# Power_Cerebro.net
KiCad netlist of a schematic drawn in Altium Designer
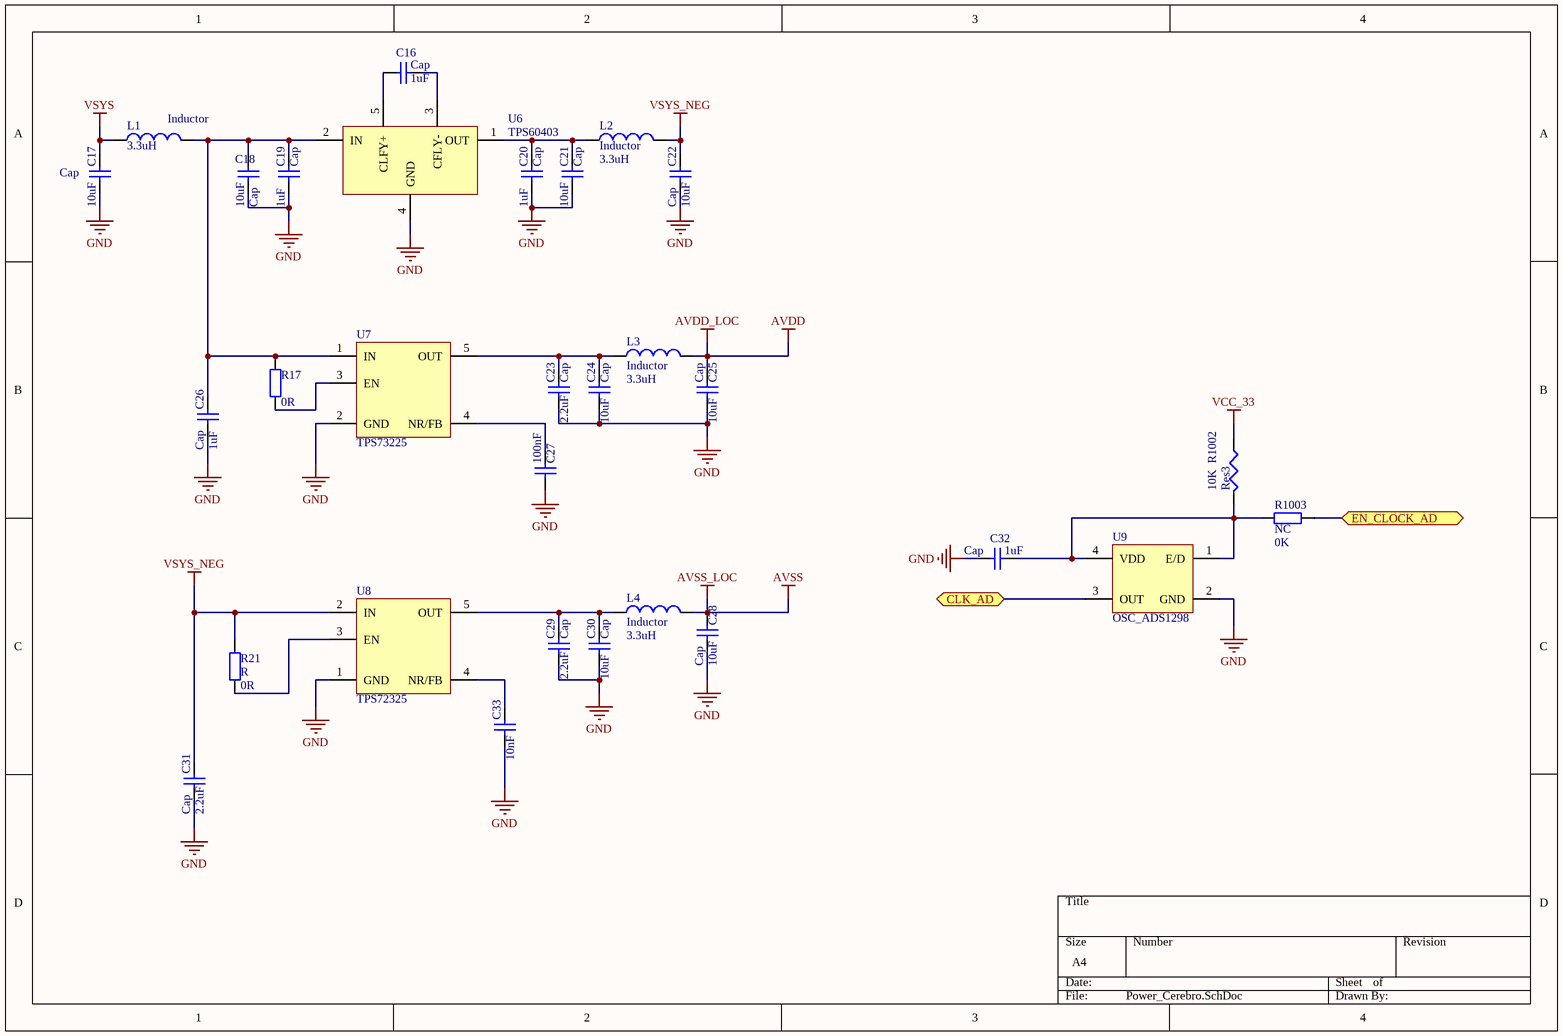
[diagram p0: Power_Cerebro.SchDoc]

(export (version "E")
  (design (tool "Eeschema 10.0.6"))
  (components
    (comp (ref "C16")
      (value "Cap")
      (footprint "cap_0402_R - modified")
      (description "Capacitor")
      (fields (field (name "ALTIUM_VALUE") "1uF") (field (name "PUBLISHER") "Altium Limited"))
      (libsource (lib "Miscellaneous Devices") (part "Cap"))
    )
    (comp (ref "C17")
      (value "Cap")
      (footprint "cap_0402_R - modified")
      (description "Capacitor")
      (fields (field (name "ALTIUM_VALUE") "10uF") (field (name "PUBLISHER") "Altium Limited"))
      (libsource (lib "Miscellaneous Devices") (part "Cap"))
    )
    (comp (ref "C18")
      (value "Cap")
      (footprint "cap_0402_R - modified")
      (description "Capacitor")
      (fields (field (name "ALTIUM_VALUE") "10uF") (field (name "PUBLISHER") "Altium Limited"))
      (libsource (lib "Miscellaneous Devices") (part "Cap"))
    )
    (comp (ref "C19")
      (value "Cap")
      (footprint "cap_0402_R - modified")
      (description "Capacitor")
      (fields (field (name "ALTIUM_VALUE") "1uF") (field (name "PUBLISHER") "Altium Limited"))
      (libsource (lib "Miscellaneous Devices") (part "Cap"))
    )
    (comp (ref "C20")
      (value "Cap")
      (footprint "cap_0402_R - modified")
      (description "Capacitor")
      (fields (field (name "ALTIUM_VALUE") "1uF") (field (name "PUBLISHER") "Altium Limited"))
      (libsource (lib "Miscellaneous Devices") (part "Cap"))
    )
    (comp (ref "C21")
      (value "Cap")
      (footprint "cap_0402_R - modified")
      (description "Capacitor")
      (fields (field (name "ALTIUM_VALUE") "10uF") (field (name "PUBLISHER") "Altium Limited"))
      (libsource (lib "Miscellaneous Devices") (part "Cap"))
    )
    (comp (ref "C22")
      (value "Cap")
      (footprint "cap_0402_R - modified")
      (description "Capacitor")
      (fields (field (name "ALTIUM_VALUE") "10uF") (field (name "PUBLISHER") "Altium Limited"))
      (libsource (lib "Miscellaneous Devices") (part "Cap"))
    )
    (comp (ref "C23")
      (value "Cap")
      (footprint "cap_0402_R - modified")
      (description "Capacitor")
      (fields (field (name "ALTIUM_VALUE") "2.2uF") (field (name "PUBLISHER") "Altium Limited"))
      (libsource (lib "Miscellaneous Devices") (part "Cap"))
    )
    (comp (ref "C24")
      (value "Cap")
      (footprint "cap_0402_R - modified")
      (description "Capacitor")
      (fields (field (name "ALTIUM_VALUE") "10uF") (field (name "PUBLISHER") "Altium Limited"))
      (libsource (lib "Miscellaneous Devices") (part "Cap"))
    )
    (comp (ref "C25")
      (value "Cap")
      (footprint "cap_0402_R - modified")
      (description "Capacitor")
      (fields (field (name "ALTIUM_VALUE") "10uF") (field (name "PUBLISHER") "Altium Limited"))
      (libsource (lib "Miscellaneous Devices") (part "Cap"))
    )
    (comp (ref "C26")
      (value "Cap")
      (footprint "cap_0402_R - modified")
      (description "Capacitor")
      (fields (field (name "ALTIUM_VALUE") "1uF") (field (name "PUBLISHER") "Altium Limited"))
      (libsource (lib "Miscellaneous Devices") (part "Cap"))
    )
    (comp (ref "C27")
      (value "100nF")
      (footprint "cap_0402_R - modified")
      (description "Capacitor")
      (fields (field (name "Comment") "C") (field (name "PUBLISHER") "Altium Limited"))
      (libsource (lib "Miscellaneous Devices") (part "Cap"))
    )
    (comp (ref "C28")
      (value "Cap")
      (footprint "cap_0402_R - modified")
      (description "Capacitor")
      (fields (field (name "ALTIUM_VALUE") "10uF") (field (name "PUBLISHER") "Altium Limited"))
      (libsource (lib "Miscellaneous Devices") (part "Cap"))
    )
    (comp (ref "C29")
      (value "Cap")
      (footprint "cap_0402_R - modified")
      (description "Capacitor")
      (fields (field (name "ALTIUM_VALUE") "2.2uF") (field (name "PUBLISHER") "Altium Limited"))
      (libsource (lib "Miscellaneous Devices") (part "Cap"))
    )
    (comp (ref "C30")
      (value "Cap")
      (footprint "cap_0402_R - modified")
      (description "Capacitor")
      (fields (field (name "ALTIUM_VALUE") "10uF") (field (name "PUBLISHER") "Altium Limited"))
      (libsource (lib "Miscellaneous Devices") (part "Cap"))
    )
    (comp (ref "C31")
      (value "Cap")
      (footprint "cap_0402_R - modified")
      (description "Capacitor")
      (fields (field (name "ALTIUM_VALUE") "2.2uF") (field (name "PUBLISHER") "Altium Limited"))
      (libsource (lib "Miscellaneous Devices") (part "Cap"))
    )
    (comp (ref "C32")
      (value "Cap")
      (footprint "cap_0402_R - modified")
      (description "Capacitor")
      (fields (field (name "ALTIUM_VALUE") "1uF") (field (name "PUBLISHER") "Altium Limited"))
      (libsource (lib "Miscellaneous Devices") (part "Cap"))
    )
    (comp (ref "C33")
      (value "10nF")
      (footprint "cap_0402_R - modified")
      (description "Capacitor")
      (fields (field (name "Comment") "C") (field (name "PUBLISHER") "Altium Limited"))
      (libsource (lib "Miscellaneous Devices") (part "Cap"))
    )
    (comp (ref "L1")
      (value "Inductor")
      (footprint "0603")
      (fields (field (name "ALTIUM_VALUE") "3.3uH") (field (name "PUBLISHER") "Altium Limited"))
      (libsource (lib "Miscellaneous Devices") (part "Inductor"))
    )
    (comp (ref "L2")
      (value "Inductor")
      (footprint "0603")
      (fields (field (name "ALTIUM_VALUE") "3.3uH") (field (name "PUBLISHER") "Altium Limited"))
      (libsource (lib "Miscellaneous Devices") (part "Inductor"))
    )
    (comp (ref "L3")
      (value "Inductor")
      (footprint "0603")
      (fields (field (name "ALTIUM_VALUE") "3.3uH") (field (name "PUBLISHER") "Altium Limited"))
      (libsource (lib "Miscellaneous Devices") (part "Inductor"))
    )
    (comp (ref "L4")
      (value "Inductor")
      (footprint "0603")
      (fields (field (name "ALTIUM_VALUE") "3.3uH") (field (name "PUBLISHER") "Altium Limited"))
      (libsource (lib "Miscellaneous Devices") (part "Inductor"))
    )
    (comp (ref "R17")
      (value "0R")
      (footprint "cap_0402_R - modified")
      (description "Resistor")
      (fields (field (name "Comment") "R") (field (name "PUBLISHER") "Altium Limited"))
      (libsource (lib "") (part "Res2_2"))
    )
    (comp (ref "R21")
      (value "R")
      (footprint "cap_0402_R - modified")
      (description "Resistor")
      (fields (field (name "ALTIUM_VALUE") "0R") (field (name "PUBLISHER") "Altium Limited"))
      (libsource (lib "") (part "Res2_1"))
    )
    (comp (ref "R1002")
      (value "Res3")
      (footprint "res_0402_R - modified")
      (description "Resistor")
      (fields (field (name "ALTIUM_VALUE") "10K") (field (name "PUBLISHER") "Altium Limited"))
      (libsource (lib "Miscellaneous Devices") (part "Res3"))
    )
    (comp (ref "R1003")
      (value "NC")
      (footprint "cap_0402_R - modified")
      (description "Resistor")
      (fields (field (name "ALTIUM_VALUE") "0K") (field (name "PUBLISHER") "Altium Limited"))
      (libsource (lib "Miscellaneous Devices") (part "Res2"))
    )
    (comp (ref "U6")
      (value "TPS60403")
      (footprint "SOT_23__DBV_(R - PDSO - G5)")
      (description "Linear Regulator")
      (libsource (lib "Demo_Board_library_SCH") (part "TPS60403"))
    )
    (comp (ref "U7")
      (value "TPS73225")
      (footprint "Demo_Board_library_PCB:SOT23__DDC__(R - PDSO-  G5)")
      (description "Linear Regulator")
      (libsource (lib "Demo_Board_library_SCH") (part "TPS73225"))
    )
    (comp (ref "U8")
      (value "TPS72325")
      (footprint "Demo_Board_library_PCB:SOT23__DDC__(R - PDSO-  G5)")
      (description "Linear Regulator")
      (libsource (lib "Demo_Board_library_SCH") (part "TPS72325"))
    )
    (comp (ref "U9")
      (value "OSC_ADS1298")
      (footprint "HC735 - OSC ADS1298")
      (description "Linear Regulator")
      (libsource (lib "Demo_Board_library_SCH") (part "OSC_ADS1298"))
    )
  )
  (nets
    (net (code "1") (name "/CLK_AD") (class "Default")
      (node (ref "U9") (pin "3") (pinfunction "OUT_3") (pintype "passive"))
    )
    (net (code "2") (name "/EN_CLOCK_AD") (class "Default")
      (node (ref "R1003") (pin "1") (pinfunction "1_1") (pintype "passive"))
    )
    (net (code "3") (name "AVDD") (class "Default")
      (node (ref "C25") (pin "1") (pinfunction "1_1") (pintype "passive"))
      (node (ref "L3") (pin "2") (pinfunction "2_2") (pintype "passive"))
    )
    (net (code "4") (name "AVSS") (class "Default")
      (node (ref "C28") (pin "1") (pinfunction "1_1") (pintype "passive"))
      (node (ref "L4") (pin "2") (pinfunction "2_2") (pintype "passive"))
    )
    (net (code "5") (name "GND") (class "Default")
      (node (ref "C17") (pin "2") (pinfunction "2_2") (pintype "passive"))
      (node (ref "C18") (pin "2") (pinfunction "2_2") (pintype "passive"))
      (node (ref "C19") (pin "2") (pinfunction "2_2") (pintype "passive"))
      (node (ref "C20") (pin "2") (pinfunction "2_2") (pintype "passive"))
      (node (ref "C21") (pin "2") (pinfunction "2_2") (pintype "passive"))
      (node (ref "C22") (pin "2") (pinfunction "2_2") (pintype "passive"))
      (node (ref "C23") (pin "2") (pinfunction "2_2") (pintype "passive"))
      (node (ref "C24") (pin "2") (pinfunction "2_2") (pintype "passive"))
      (node (ref "C25") (pin "2") (pinfunction "2_2") (pintype "passive"))
      (node (ref "C26") (pin "2") (pinfunction "2_2") (pintype "passive"))
      (node (ref "C27") (pin "2") (pinfunction "2_2") (pintype "passive"))
      (node (ref "C28") (pin "2") (pinfunction "2_2") (pintype "passive"))
      (node (ref "C29") (pin "2") (pinfunction "2_2") (pintype "passive"))
      (node (ref "C30") (pin "2") (pinfunction "2_2") (pintype "passive"))
      (node (ref "C31") (pin "2") (pinfunction "2_2") (pintype "passive"))
      (node (ref "C32") (pin "2") (pinfunction "2_2") (pintype "passive"))
      (node (ref "C33") (pin "2") (pinfunction "2_2") (pintype "passive"))
      (node (ref "U6") (pin "4") (pinfunction "GND_4") (pintype "passive"))
      (node (ref "U7") (pin "2") (pinfunction "GND_2") (pintype "passive"))
      (node (ref "U8") (pin "1") (pinfunction "GND_1") (pintype "passive"))
      (node (ref "U9") (pin "2") (pinfunction "GND_2") (pintype "passive"))
    )
    (net (code "6") (name "Net-(U6-CFLY-)") (class "Default")
      (node (ref "C16") (pin "1") (pinfunction "1_1") (pintype "passive"))
      (node (ref "U6") (pin "3") (pinfunction "CFLY-_3") (pintype "passive"))
    )
    (net (code "7") (name "Net-(U6-CLFY+)") (class "Default")
      (node (ref "C16") (pin "2") (pinfunction "2_2") (pintype "passive"))
      (node (ref "U6") (pin "5") (pinfunction "CLFY+_5") (pintype "passive"))
    )
    (net (code "8") (name "Net-(U6-IN)") (class "Default")
      (node (ref "C18") (pin "1") (pinfunction "1_1") (pintype "passive"))
      (node (ref "C19") (pin "1") (pinfunction "1_1") (pintype "passive"))
      (node (ref "C26") (pin "1") (pinfunction "1_1") (pintype "passive"))
      (node (ref "L1") (pin "2") (pinfunction "2_2") (pintype "passive"))
      (node (ref "R17") (pin "2") (pinfunction "2_2") (pintype "passive"))
      (node (ref "U6") (pin "2") (pinfunction "IN_2") (pintype "passive"))
      (node (ref "U7") (pin "1") (pinfunction "IN_1") (pintype "passive"))
    )
    (net (code "9") (name "Net-(U6-OUT)") (class "Default")
      (node (ref "C20") (pin "1") (pinfunction "1_1") (pintype "passive"))
      (node (ref "C21") (pin "1") (pinfunction "1_1") (pintype "passive"))
      (node (ref "L2") (pin "1") (pinfunction "1_1") (pintype "passive"))
      (node (ref "U6") (pin "1") (pinfunction "OUT_1") (pintype "passive"))
    )
    (net (code "10") (name "Net-(U7-EN)") (class "Default")
      (node (ref "R17") (pin "1") (pinfunction "1_1") (pintype "passive"))
      (node (ref "U7") (pin "3") (pinfunction "EN_3") (pintype "passive"))
    )
    (net (code "11") (name "Net-(U7-NR{slash}FB)") (class "Default")
      (node (ref "C27") (pin "1") (pinfunction "1_1") (pintype "passive"))
      (node (ref "U7") (pin "4") (pinfunction "NR/FB_4") (pintype "passive"))
    )
    (net (code "12") (name "Net-(U7-OUT)") (class "Default")
      (node (ref "C23") (pin "1") (pinfunction "1_1") (pintype "passive"))
      (node (ref "C24") (pin "1") (pinfunction "1_1") (pintype "passive"))
      (node (ref "L3") (pin "1") (pinfunction "1_1") (pintype "passive"))
      (node (ref "U7") (pin "5") (pinfunction "OUT_5") (pintype "passive"))
    )
    (net (code "13") (name "Net-(U8-EN)") (class "Default")
      (node (ref "R21") (pin "2") (pinfunction "2_2") (pintype "passive"))
      (node (ref "U8") (pin "3") (pinfunction "EN_3") (pintype "passive"))
    )
    (net (code "14") (name "Net-(U8-NR{slash}FB)") (class "Default")
      (node (ref "C33") (pin "1") (pinfunction "1_1") (pintype "passive"))
      (node (ref "U8") (pin "4") (pinfunction "NR/FB_4") (pintype "passive"))
    )
    (net (code "15") (name "Net-(U8-OUT)") (class "Default")
      (node (ref "C29") (pin "1") (pinfunction "1_1") (pintype "passive"))
      (node (ref "C30") (pin "1") (pinfunction "1_1") (pintype "passive"))
      (node (ref "L4") (pin "1") (pinfunction "1_1") (pintype "passive"))
      (node (ref "U8") (pin "5") (pinfunction "OUT_5") (pintype "passive"))
    )
    (net (code "16") (name "Net-(U9-E{slash}D)") (class "Default")
      (node (ref "C32") (pin "1") (pinfunction "1_1") (pintype "passive"))
      (node (ref "R1002") (pin "2") (pinfunction "2_2") (pintype "passive"))
      (node (ref "R1003") (pin "2") (pinfunction "2_2") (pintype "passive"))
      (node (ref "U9") (pin "1") (pinfunction "E/D_1") (pintype "passive"))
      (node (ref "U9") (pin "4") (pinfunction "VDD_4") (pintype "passive"))
    )
    (net (code "17") (name "VCC_33") (class "Default")
      (node (ref "R1002") (pin "1") (pinfunction "1_1") (pintype "passive"))
    )
    (net (code "18") (name "VSYS") (class "Default")
      (node (ref "C17") (pin "1") (pinfunction "1_1") (pintype "passive"))
      (node (ref "L1") (pin "1") (pinfunction "1_1") (pintype "passive"))
    )
    (net (code "19") (name "VSYS_NEG") (class "Default")
      (node (ref "C22") (pin "1") (pinfunction "1_1") (pintype "passive"))
      (node (ref "C31") (pin "1") (pinfunction "1_1") (pintype "passive"))
      (node (ref "L2") (pin "2") (pinfunction "2_2") (pintype "passive"))
      (node (ref "R21") (pin "1") (pinfunction "1_1") (pintype "passive"))
      (node (ref "U8") (pin "2") (pinfunction "IN_2") (pintype "passive"))
    )
  )
)
